# charLED.net
KiCad netlist of a schematic drawn in EAGLE
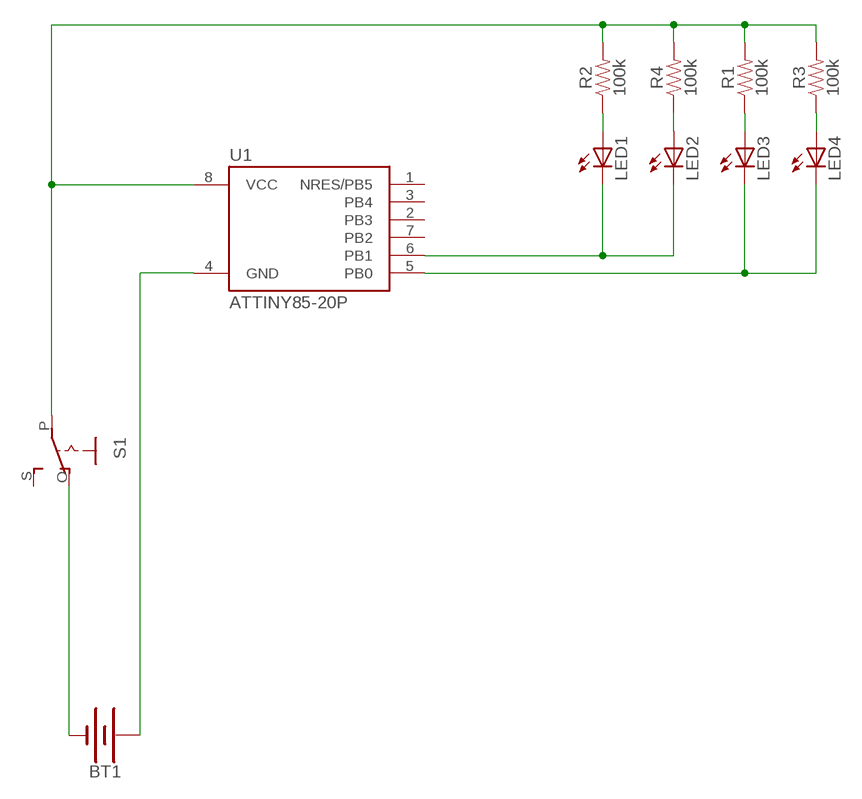
[diagram p0: schematic, sheet 1]

(export (version "E")
  (design (tool "Eeschema 10.0.6"))
  (components
    (comp (ref "BT1")
      (value "BATTERY-20MM_PTH")
      (footprint "eagle-import:BATTCOM_20MM_PTH")
      (libsource (lib "eagle-import") (part "BATTERY-20MM_PTH"))
    )
    (comp (ref "LED1")
      (value "LED5MM")
      (footprint "eagle-import:LED5MM")
      (libsource (lib "eagle-import") (part "LED5MM"))
    )
    (comp (ref "LED2")
      (value "LED5MM")
      (footprint "eagle-import:LED5MM")
      (libsource (lib "eagle-import") (part "LED5MM"))
    )
    (comp (ref "LED3")
      (value "LED5MM")
      (footprint "eagle-import:LED5MM")
      (libsource (lib "eagle-import") (part "LED5MM"))
    )
    (comp (ref "LED4")
      (value "LED5MM")
      (footprint "eagle-import:LED5MM")
      (libsource (lib "eagle-import") (part "LED5MM"))
    )
    (comp (ref "R1")
      (value "100k")
      (footprint "eagle-import:AXIAL-0.3")
      (libsource (lib "eagle-import") (part "100KOHM-HORIZ-1/4W-1%"))
    )
    (comp (ref "R2")
      (value "100k")
      (footprint "eagle-import:AXIAL-0.3")
      (libsource (lib "eagle-import") (part "100KOHM-HORIZ-1/4W-1%"))
    )
    (comp (ref "R3")
      (value "100k")
      (footprint "eagle-import:AXIAL-0.3")
      (libsource (lib "eagle-import") (part "100KOHM-HORIZ-1/4W-1%"))
    )
    (comp (ref "R4")
      (value "100k")
      (footprint "eagle-import:AXIAL-0.3")
      (libsource (lib "eagle-import") (part "100KOHM-HORIZ-1/4W-1%"))
    )
    (comp (ref "S1")
      (value "EG1218S")
      (footprint "eagle-import:EG1218")
      (libsource (lib "eagle-import") (part "EG1218S"))
    )
    (comp (ref "U1")
      (value "ATTINY85-20P")
      (footprint "eagle-import:PDIP08_300MIL")
      (libsource (lib "eagle-import") (part "ATTINY85P-20"))
    )
  )
  (nets
    (net (code "1") (name "Net-(BT1-+)") (class "Default")
      (node (ref "BT1") (pin "1") (pinfunction "+_1") (pintype "power_in"))
      (node (ref "U1") (pin "4") (pinfunction "GND_4") (pintype "power_in"))
    )
    (net (code "2") (name "Net-(BT1--)") (class "Default")
      (node (ref "BT1") (pin "2") (pinfunction "-_2") (pintype "power_in"))
      (node (ref "S1") (pin "O") (pinfunction "O_O") (pintype "passive"))
    )
    (net (code "3") (name "Net-(LED1-C)") (class "Default")
      (node (ref "LED1") (pin "K") (pinfunction "C_K") (pintype "passive"))
      (node (ref "LED2") (pin "K") (pinfunction "C_K") (pintype "passive"))
      (node (ref "U1") (pin "6") (pinfunction "PB1_6") (pintype "bidirectional"))
    )
    (net (code "4") (name "Net-(LED3-C)") (class "Default")
      (node (ref "LED3") (pin "K") (pinfunction "C_K") (pintype "passive"))
      (node (ref "LED4") (pin "K") (pinfunction "C_K") (pintype "passive"))
      (node (ref "U1") (pin "5") (pinfunction "PB0_5") (pintype "bidirectional"))
    )
    (net (code "5") (name "Net-(R1-1)") (class "Default")
      (node (ref "LED3") (pin "A") (pinfunction "A_A") (pintype "passive"))
      (node (ref "R1") (pin "P$1") (pinfunction "1_P$1") (pintype "passive"))
    )
    (net (code "6") (name "Net-(R1-2)") (class "Default")
      (node (ref "R1") (pin "P$2") (pinfunction "2_P$2") (pintype "passive"))
      (node (ref "R2") (pin "P$2") (pinfunction "2_P$2") (pintype "passive"))
      (node (ref "R3") (pin "P$2") (pinfunction "2_P$2") (pintype "passive"))
      (node (ref "R4") (pin "P$2") (pinfunction "2_P$2") (pintype "passive"))
      (node (ref "S1") (pin "P") (pinfunction "P_P") (pintype "passive"))
      (node (ref "U1") (pin "8") (pinfunction "VCC_8") (pintype "power_in"))
    )
    (net (code "7") (name "Net-(R2-1)") (class "Default")
      (node (ref "LED1") (pin "A") (pinfunction "A_A") (pintype "passive"))
      (node (ref "R2") (pin "P$1") (pinfunction "1_P$1") (pintype "passive"))
    )
    (net (code "8") (name "Net-(R3-1)") (class "Default")
      (node (ref "LED4") (pin "A") (pinfunction "A_A") (pintype "passive"))
      (node (ref "R3") (pin "P$1") (pinfunction "1_P$1") (pintype "passive"))
    )
    (net (code "9") (name "Net-(R4-1)") (class "Default")
      (node (ref "LED2") (pin "A") (pinfunction "A_A") (pintype "passive"))
      (node (ref "R4") (pin "P$1") (pinfunction "1_P$1") (pintype "passive"))
    )
    (net (code "10") (name "unconnected-(S1-PadS)") (class "Default")
      (node (ref "S1") (pin "S") (pinfunction "S_S") (pintype "passive"))
    )
    (net (code "11") (name "unconnected-(U1-NRES{slash}PB5-Pad1)") (class "Default")
      (node (ref "U1") (pin "1") (pinfunction "NRES/PB5_1") (pintype "bidirectional"))
    )
    (net (code "12") (name "unconnected-(U1-PB2-Pad7)") (class "Default")
      (node (ref "U1") (pin "7") (pinfunction "PB2_7") (pintype "bidirectional"))
    )
    (net (code "13") (name "unconnected-(U1-PB3-Pad2)") (class "Default")
      (node (ref "U1") (pin "2") (pinfunction "PB3_2") (pintype "bidirectional"))
    )
    (net (code "14") (name "unconnected-(U1-PB4-Pad3)") (class "Default")
      (node (ref "U1") (pin "3") (pinfunction "PB4_3") (pintype "bidirectional"))
    )
  )
)
